# S3220A2.net
KiCad netlist of a schematic drawn in Altium Designer
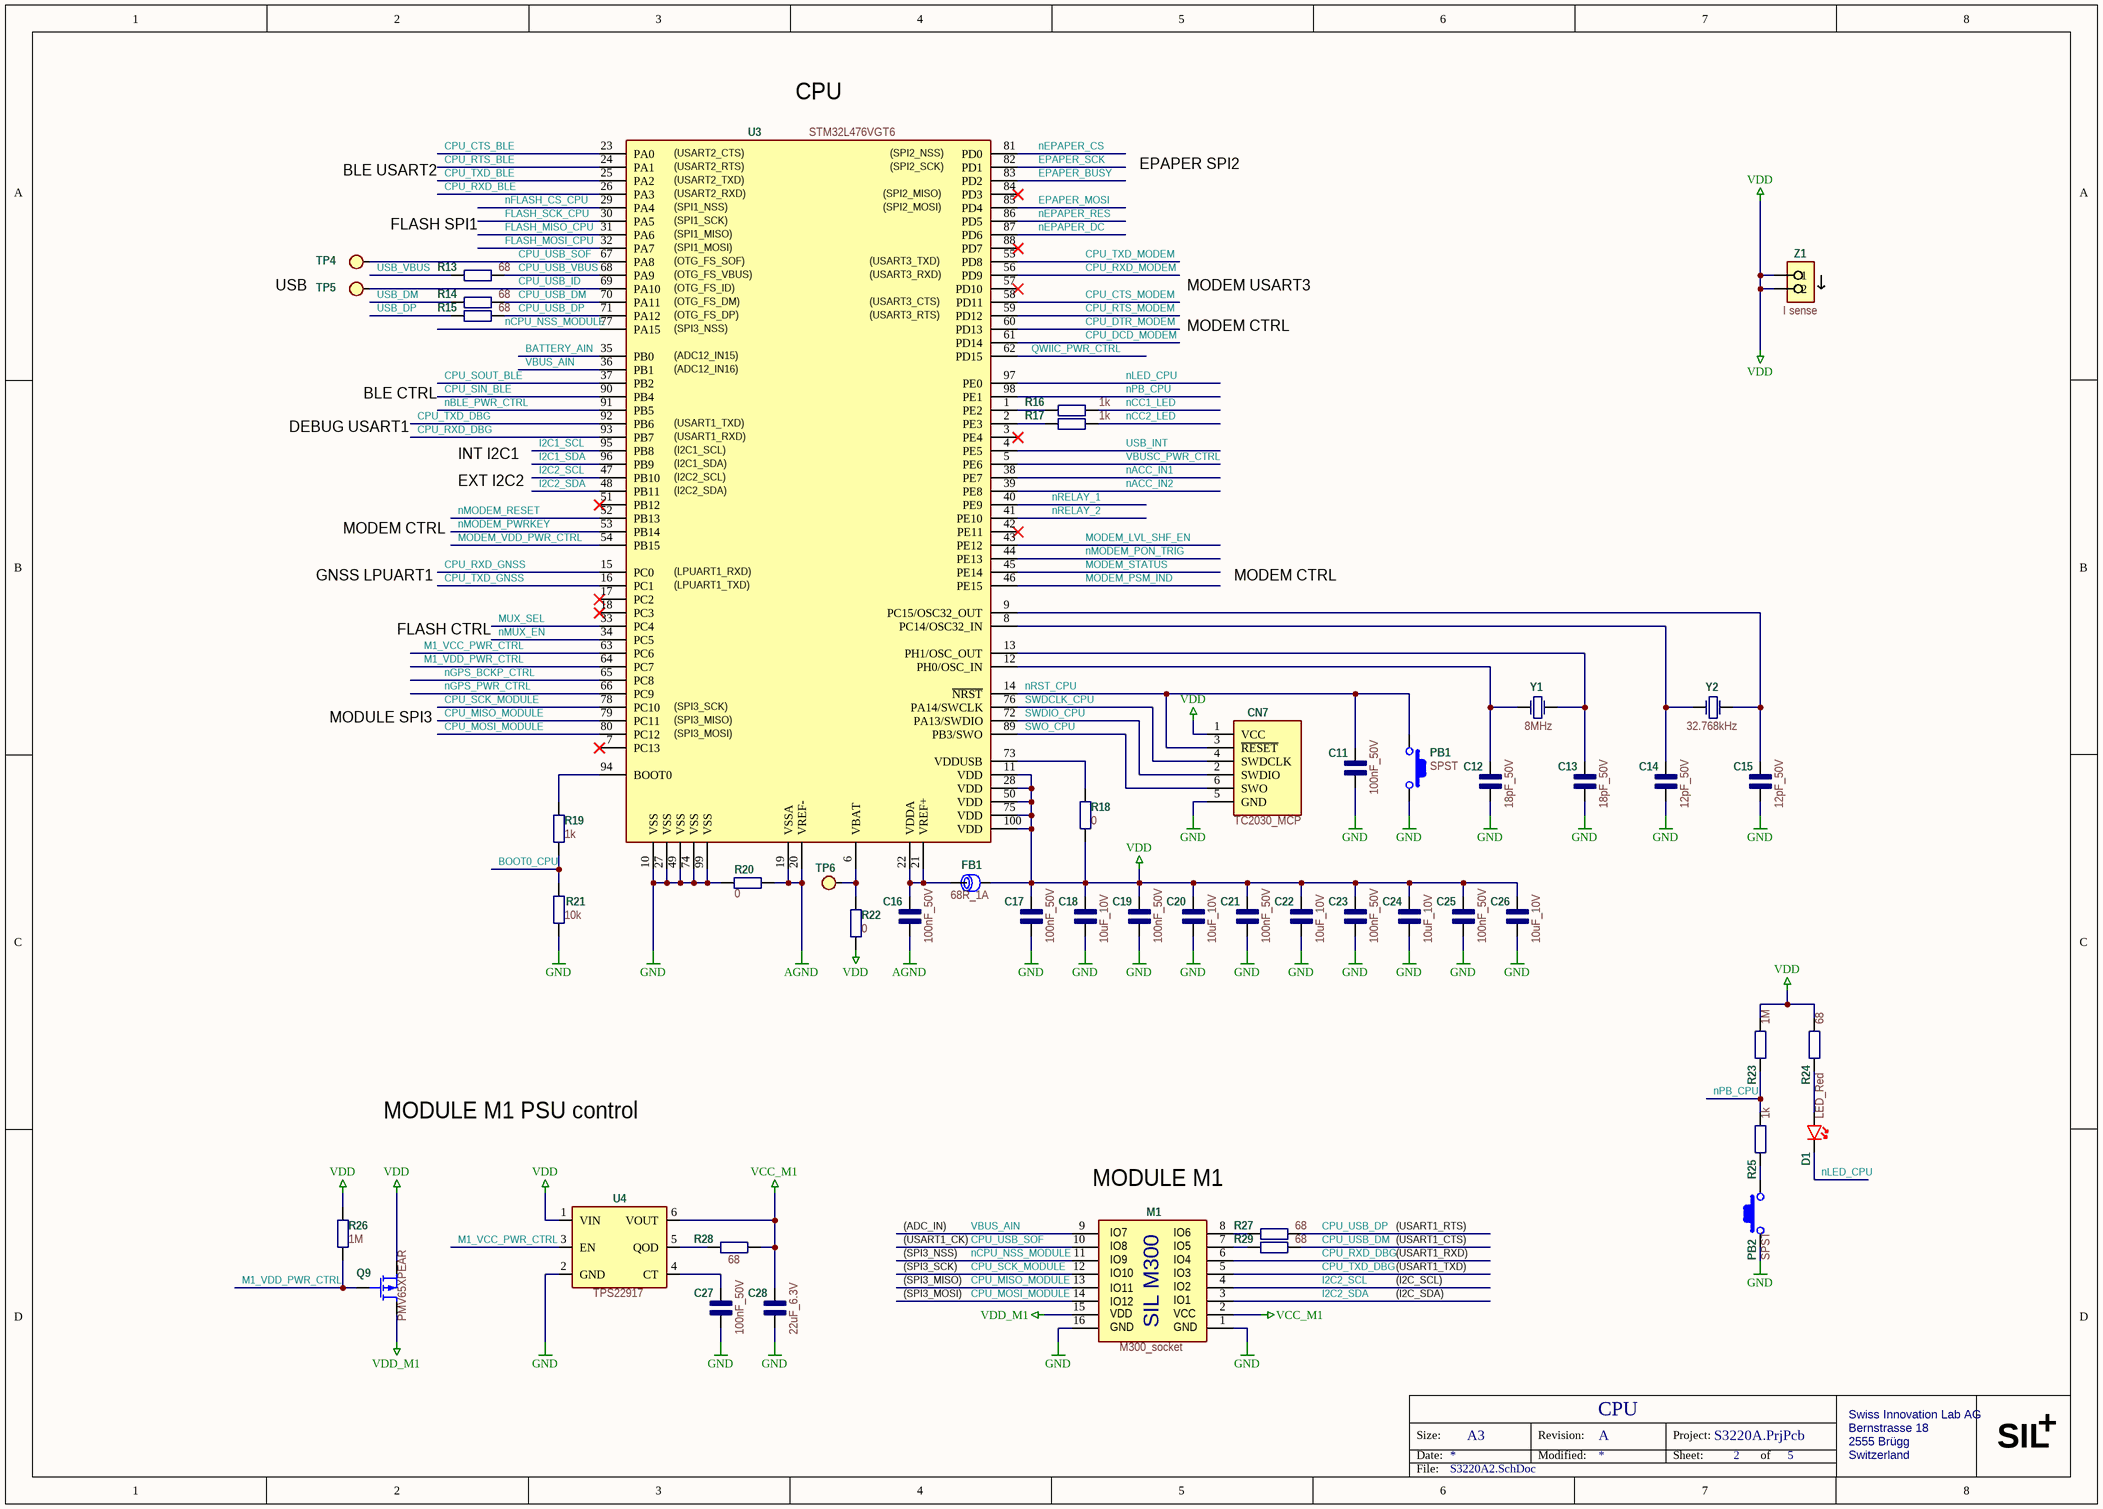
[diagram p0: S3220A2.SchDoc]

(export (version "E")
  (design (tool "Eeschema 10.0.6"))
  (components
    (comp (ref "C11")
      (value "100nF_50V")
      (footprint "SIL:C_0603")
      (description "0.1µF ±10% 50V Ceramic Capacitor X7R 0603 (1608 Metric)")
      (fields
        (field (name "MANUFACTURER") "TDK")
        (field (name "MANUFACTURER PART NUMBER") "C1608X7R1H104K080AA")
      )
      (libsource (lib "SIL") (part "C_100nF_50V"))
    )
    (comp (ref "C12")
      (value "18pF_50V")
      (footprint "SIL:C_0603")
      (description "18pF ±5% 50V Ceramic Capacitor C0G, NP0 0603 (1608 Metric)")
      (fields
        (field (name "MANUFACTURER") "KEMET")
        (field (name "MANUFACTURER PART NUMBER") "C0603C180J5GACTU")
      )
      (libsource (lib "SIL") (part "C_18pF_50V"))
    )
    (comp (ref "C13")
      (value "18pF_50V")
      (footprint "SIL:C_0603")
      (description "18pF ±5% 50V Ceramic Capacitor C0G, NP0 0603 (1608 Metric)")
      (fields
        (field (name "MANUFACTURER") "KEMET")
        (field (name "MANUFACTURER PART NUMBER") "C0603C180J5GACTU")
      )
      (libsource (lib "SIL") (part "C_18pF_50V"))
    )
    (comp (ref "C14")
      (value "12pF_50V")
      (footprint "SIL:C_0603")
      (description "12pF ±1% 50V Ceramic Capacitor C0G, NP0 0603 (1608 Metric)")
      (fields
        (field (name "MANUFACTURER") "Samsung Electro-Mechanics")
        (field (name "MANUFACTURER PART NUMBER") "CL10C120FB8NNNC")
      )
      (libsource (lib "SIL") (part "C_12pF_50V"))
    )
    (comp (ref "C15")
      (value "12pF_50V")
      (footprint "SIL:C_0603")
      (description "12pF ±1% 50V Ceramic Capacitor C0G, NP0 0603 (1608 Metric)")
      (fields
        (field (name "MANUFACTURER") "Samsung Electro-Mechanics")
        (field (name "MANUFACTURER PART NUMBER") "CL10C120FB8NNNC")
      )
      (libsource (lib "SIL") (part "C_12pF_50V"))
    )
    (comp (ref "C16")
      (value "100nF_50V")
      (footprint "SIL:C_0603")
      (description "0.1µF ±10% 50V Ceramic Capacitor X7R 0603 (1608 Metric)")
      (fields
        (field (name "MANUFACTURER") "TDK")
        (field (name "MANUFACTURER PART NUMBER") "C1608X7R1H104K080AA")
      )
      (libsource (lib "SIL") (part "C_100nF_50V"))
    )
    (comp (ref "C17")
      (value "100nF_50V")
      (footprint "SIL:C_0603")
      (description "0.1µF ±10% 50V Ceramic Capacitor X7R 0603 (1608 Metric)")
      (fields
        (field (name "MANUFACTURER") "TDK")
        (field (name "MANUFACTURER PART NUMBER") "C1608X7R1H104K080AA")
      )
      (libsource (lib "SIL") (part "C_100nF_50V"))
    )
    (comp (ref "C18")
      (value "10uF_10V")
      (footprint "SIL:C_0603")
      (description "10µF ±10% 10V Ceramic Capacitor X5R 0603 (1608 Metric)")
      (fields
        (field (name "MANUFACTURER") "Murata Electronics North America")
        (field (name "MANUFACTURER PART NUMBER") "GRM188R61A106KE69D")
      )
      (libsource (lib "SIL") (part "C_10uF_10V"))
    )
    (comp (ref "C19")
      (value "100nF_50V")
      (footprint "SIL:C_0603")
      (description "0.1µF ±10% 50V Ceramic Capacitor X7R 0603 (1608 Metric)")
      (fields
        (field (name "MANUFACTURER") "TDK")
        (field (name "MANUFACTURER PART NUMBER") "C1608X7R1H104K080AA")
      )
      (libsource (lib "SIL") (part "C_100nF_50V"))
    )
    (comp (ref "C20")
      (value "10uF_10V")
      (footprint "SIL:C_0603")
      (description "10µF ±10% 10V Ceramic Capacitor X5R 0603 (1608 Metric)")
      (fields
        (field (name "MANUFACTURER") "Murata Electronics North America")
        (field (name "MANUFACTURER PART NUMBER") "GRM188R61A106KE69D")
      )
      (libsource (lib "SIL") (part "C_10uF_10V"))
    )
    (comp (ref "C21")
      (value "100nF_50V")
      (footprint "SIL:C_0603")
      (description "0.1µF ±10% 50V Ceramic Capacitor X7R 0603 (1608 Metric)")
      (fields
        (field (name "MANUFACTURER") "TDK")
        (field (name "MANUFACTURER PART NUMBER") "C1608X7R1H104K080AA")
      )
      (libsource (lib "SIL") (part "C_100nF_50V"))
    )
    (comp (ref "C22")
      (value "10uF_10V")
      (footprint "SIL:C_0603")
      (description "10µF ±10% 10V Ceramic Capacitor X5R 0603 (1608 Metric)")
      (fields
        (field (name "MANUFACTURER") "Murata Electronics North America")
        (field (name "MANUFACTURER PART NUMBER") "GRM188R61A106KE69D")
      )
      (libsource (lib "SIL") (part "C_10uF_10V"))
    )
    (comp (ref "C23")
      (value "100nF_50V")
      (footprint "SIL:C_0603")
      (description "0.1µF ±10% 50V Ceramic Capacitor X7R 0603 (1608 Metric)")
      (fields
        (field (name "MANUFACTURER") "TDK")
        (field (name "MANUFACTURER PART NUMBER") "C1608X7R1H104K080AA")
      )
      (libsource (lib "SIL") (part "C_100nF_50V"))
    )
    (comp (ref "C24")
      (value "10uF_10V")
      (footprint "SIL:C_0603")
      (description "10µF ±10% 10V Ceramic Capacitor X5R 0603 (1608 Metric)")
      (fields
        (field (name "MANUFACTURER") "Murata Electronics North America")
        (field (name "MANUFACTURER PART NUMBER") "GRM188R61A106KE69D")
      )
      (libsource (lib "SIL") (part "C_10uF_10V"))
    )
    (comp (ref "C25")
      (value "100nF_50V")
      (footprint "SIL:C_0603")
      (description "0.1µF ±10% 50V Ceramic Capacitor X7R 0603 (1608 Metric)")
      (fields
        (field (name "MANUFACTURER") "TDK")
        (field (name "MANUFACTURER PART NUMBER") "C1608X7R1H104K080AA")
      )
      (libsource (lib "SIL") (part "C_100nF_50V"))
    )
    (comp (ref "C26")
      (value "10uF_10V")
      (footprint "SIL:C_0603")
      (description "10µF ±10% 10V Ceramic Capacitor X5R 0603 (1608 Metric)")
      (fields
        (field (name "MANUFACTURER") "Murata Electronics North America")
        (field (name "MANUFACTURER PART NUMBER") "GRM188R61A106KE69D")
      )
      (libsource (lib "SIL") (part "C_10uF_10V"))
    )
    (comp (ref "C27")
      (value "100nF_50V")
      (footprint "SIL:C_0603")
      (description "0.1µF ±10% 50V Ceramic Capacitor X7R 0603 (1608 Metric)")
      (fields
        (field (name "MANUFACTURER") "TDK")
        (field (name "MANUFACTURER PART NUMBER") "C1608X7R1H104K080AA")
      )
      (libsource (lib "SIL") (part "C_100nF_50V"))
    )
    (comp (ref "C28")
      (value "22uF_6.3V")
      (footprint "SIL:C_0603")
      (description "22µF ±20% 6.3V Ceramic Capacitor X5R 0603 (1608 Metric)")
      (fields
        (field (name "MANUFACTURER") "Samsung Electro-Mechanics")
        (field (name "MANUFACTURER PART NUMBER") "CL10A226MQ8NRNC")
      )
      (libsource (lib "SIL") (part "C_22uF_6V3"))
    )
    (comp (ref "CN7")
      (value "TC2030_MCP")
      (footprint "SIL:CN_TC2030-MCP-NL")
      (description "TC2030-MCP-NL")
      (libsource (lib "SIL") (part "CN_TC2030"))
    )
    (comp (ref "D1")
      (value "LED_Red")
      (footprint "LED_0603")
      (description "Red 631nm LED Indication - Discrete 2V 0603")
      (fields
        (field (name "MANUFACTURER") "Lite-On Inc.")
        (field (name "MANUFACTURER PART NUMBER") "LTST-C193KRKT-5A")
      )
      (libsource (lib "SIL") (part "D_LED_R_5mA"))
    )
    (comp (ref "FB1")
      (value "68R_1A")
      (footprint "SIL:L_0603")
      (description "FERRITE BEAD 68 OHM 0603 1LN")
      (fields
        (field (name "MANUFACTURER") "Laird-Signal Integrity Products")
        (field (name "MANUFACTURER PART NUMBER") "MI0603J680R-10")
      )
      (libsource (lib "SIL") (part "FB_68R_1A"))
    )
    (comp (ref "M1")
      (value "M300_socket")
      (footprint "M_M300_socket")
      (description "Module M300 motherboard socket")
      (fields
        (field (name "MANUFACTURER") "Swiss Innovation Lab")
        (field (name "MANUFACTURER PART NUMBER") "M300")
      )
      (libsource (lib "SIL") (part "M_M300_socket"))
    )
    (comp (ref "PB1")
      (value "SPST")
      (footprint "SIL:PB_PTS810")
      (description "Tactile Switch SPST-NO Top Actuated Surface Mount")
      (fields
        (field (name "MANUFACTURER") "C&K")
        (field (name "MANUFACTURER PART NUMBER") "PTS810 SJM 250 SMTR LFS")
      )
      (libsource (lib "SIL") (part "PB_SPST_2.5mm"))
    )
    (comp (ref "PB2")
      (value "SPST")
      (footprint "SIL:PB_PTS810")
      (description "Tactile Switch SPST-NO Top Actuated Surface Mount")
      (fields
        (field (name "MANUFACTURER") "C&K")
        (field (name "MANUFACTURER PART NUMBER") "PTS810 SJM 250 SMTR LFS")
      )
      (libsource (lib "SIL") (part "PB_SPST_2.5mm"))
    )
    (comp (ref "Q9")
      (value "PMV65XPEAR")
      (footprint "U_SOT23-3")
      (description "P-Channel 20V 2.8A (Ta) 480mW (Ta), 6.25W (Tc) Surface Mount TO-236AB (SOT23)")
      (fields (field (name "MANUFACTURER") "Nexperia USA Inc."))
      (libsource (lib "SIL") (part "Q_PMV65"))
    )
    (comp (ref "R13")
      (value "68")
      (footprint "SIL:R_0603")
      (description "68 Ohms ±1% 0.1W, 1/10W Chip Resistor 0603 (1608 Metric) Automotive AEC-Q200 Thick Film")
      (fields
        (field (name "MANUFACTURER") "Panasonic Electronic Components")
        (field (name "MANUFACTURER PART NUMBER") "ERJ-3EKF68R0V")
      )
      (libsource (lib "") (part "R_68_1%_1"))
    )
    (comp (ref "R14")
      (value "68")
      (footprint "SIL:R_0603")
      (description "68 Ohms ±1% 0.1W, 1/10W Chip Resistor 0603 (1608 Metric) Automotive AEC-Q200 Thick Film")
      (fields
        (field (name "MANUFACTURER") "Panasonic Electronic Components")
        (field (name "MANUFACTURER PART NUMBER") "ERJ-3EKF68R0V")
      )
      (libsource (lib "") (part "R_68_1%_1"))
    )
    (comp (ref "R15")
      (value "68")
      (footprint "SIL:R_0603")
      (description "68 Ohms ±1% 0.1W, 1/10W Chip Resistor 0603 (1608 Metric) Automotive AEC-Q200 Thick Film")
      (fields
        (field (name "MANUFACTURER") "Panasonic Electronic Components")
        (field (name "MANUFACTURER PART NUMBER") "ERJ-3EKF68R0V")
      )
      (libsource (lib "") (part "R_68_1%_1"))
    )
    (comp (ref "R16")
      (value "1k")
      (footprint "SIL:R_0603")
      (description "1 kOhms ±1% 0.1W, 1/10W Chip Resistor 0603 (1608 Metric) Automotive AEC-Q200 Thick Film")
      (fields
        (field (name "MANUFACTURER") "Panasonic Electronic Components")
        (field (name "MANUFACTURER PART NUMBER") "ERJ-3EKF1001V")
      )
      (libsource (lib "") (part "R_1k_1%_1"))
    )
    (comp (ref "R17")
      (value "1k")
      (footprint "SIL:R_0603")
      (description "1 kOhms ±1% 0.1W, 1/10W Chip Resistor 0603 (1608 Metric) Automotive AEC-Q200 Thick Film")
      (fields
        (field (name "MANUFACTURER") "Panasonic Electronic Components")
        (field (name "MANUFACTURER PART NUMBER") "ERJ-3EKF1001V")
      )
      (libsource (lib "") (part "R_1k_1%_1"))
    )
    (comp (ref "R18")
      (value "0")
      (footprint "SIL:R_0603")
      (description "0 Ohms Jumper 0.1W, 1/10W Chip Resistor 0603 (1608 Metric) Automotive AEC-Q200 Thick Film")
      (fields
        (field (name "MANUFACTURER") "Panasonic Electronic Components")
        (field (name "MANUFACTURER PART NUMBER") "ERJ-3GEY0R00V")
      )
      (libsource (lib "") (part "R_0_1%_1"))
    )
    (comp (ref "R19")
      (value "1k")
      (footprint "SIL:R_0603")
      (description "1 kOhms ±1% 0.1W, 1/10W Chip Resistor 0603 (1608 Metric) Automotive AEC-Q200 Thick Film")
      (fields
        (field (name "MANUFACTURER") "Panasonic Electronic Components")
        (field (name "MANUFACTURER PART NUMBER") "ERJ-3EKF1001V")
      )
      (libsource (lib "SIL") (part "R_1k_1%"))
    )
    (comp (ref "R20")
      (value "0")
      (footprint "SIL:R_0603")
      (description "0 Ohms Jumper 0.1W, 1/10W Chip Resistor 0603 (1608 Metric) Automotive AEC-Q200 Thick Film")
      (fields
        (field (name "MANUFACTURER") "Panasonic Electronic Components")
        (field (name "MANUFACTURER PART NUMBER") "ERJ-3GEY0R00V")
      )
      (libsource (lib "") (part "R_0_1%_2"))
    )
    (comp (ref "R21")
      (value "10k")
      (footprint "SIL:R_0603")
      (description "10 kOhms ±1% 0.1W, 1/10W Chip Resistor 0603 (1608 Metric) Automotive AEC-Q200 Thick Film")
      (fields
        (field (name "MANUFACTURER") "Panasonic Electronic Components")
        (field (name "MANUFACTURER PART NUMBER") "ERJ-3EKF1002V")
      )
      (libsource (lib "SIL") (part "R_10k_1%"))
    )
    (comp (ref "R22")
      (value "0")
      (footprint "SIL:R_0603")
      (description "0 Ohms Jumper 0.1W, 1/10W Chip Resistor 0603 (1608 Metric) Automotive AEC-Q200 Thick Film")
      (fields
        (field (name "MANUFACTURER") "Panasonic Electronic Components")
        (field (name "MANUFACTURER PART NUMBER") "ERJ-3GEY0R00V")
      )
      (libsource (lib "SIL") (part "R_0_1%"))
    )
    (comp (ref "R23")
      (value "1M")
      (footprint "SIL:R_0603")
      (description "1 MOhms ±1% 0.1W, 1/10W Chip Resistor 0603 (1608 Metric) Automotive AEC-Q200 Thick Film")
      (fields
        (field (name "MANUFACTURER") "Panasonic Electronic Components")
        (field (name "MANUFACTURER PART NUMBER") "ERJ-3EKF1004V")
      )
      (libsource (lib "") (part "R_1M_1%_1"))
    )
    (comp (ref "R24")
      (value "68")
      (footprint "SIL:R_0603")
      (description "68 Ohms ±1% 0.1W, 1/10W Chip Resistor 0603 (1608 Metric) Automotive AEC-Q200 Thick Film")
      (fields
        (field (name "MANUFACTURER") "Panasonic Electronic Components")
        (field (name "MANUFACTURER PART NUMBER") "ERJ-3EKF68R0V")
      )
      (libsource (lib "SIL") (part "R_68_1%"))
    )
    (comp (ref "R25")
      (value "1k")
      (footprint "SIL:R_0603")
      (description "1 kOhms ±1% 0.1W, 1/10W Chip Resistor 0603 (1608 Metric) Automotive AEC-Q200 Thick Film")
      (fields
        (field (name "MANUFACTURER") "Panasonic Electronic Components")
        (field (name "MANUFACTURER PART NUMBER") "ERJ-3EKF1001V")
      )
      (libsource (lib "SIL") (part "R_1k_1%"))
    )
    (comp (ref "R26")
      (value "1M")
      (footprint "SIL:R_0603")
      (description "1 MOhms ±1% 0.1W, 1/10W Chip Resistor 0603 (1608 Metric) Automotive AEC-Q200 Thick Film")
      (fields
        (field (name "MANUFACTURER") "Panasonic Electronic Components")
        (field (name "MANUFACTURER PART NUMBER") "ERJ-3EKF1004V")
      )
      (libsource (lib "SIL") (part "R_1M_1%"))
    )
    (comp (ref "R27")
      (value "68")
      (footprint "SIL:R_0603")
      (description "68 Ohms ±1% 0.1W, 1/10W Chip Resistor 0603 (1608 Metric) Automotive AEC-Q200 Thick Film")
      (fields
        (field (name "MANUFACTURER") "Panasonic Electronic Components")
        (field (name "MANUFACTURER PART NUMBER") "ERJ-3EKF68R0V")
      )
      (libsource (lib "") (part "R_68_1%_1"))
    )
    (comp (ref "R28")
      (value "68")
      (footprint "SIL:R_0603")
      (description "68 Ohms ±1% 0.1W, 1/10W Chip Resistor 0603 (1608 Metric) Automotive AEC-Q200 Thick Film")
      (fields
        (field (name "MANUFACTURER") "Panasonic Electronic Components")
        (field (name "MANUFACTURER PART NUMBER") "ERJ-3EKF68R0V")
      )
      (libsource (lib "") (part "R_68_1%_2"))
    )
    (comp (ref "R29")
      (value "68")
      (footprint "SIL:R_0603")
      (description "68 Ohms ±1% 0.1W, 1/10W Chip Resistor 0603 (1608 Metric) Automotive AEC-Q200 Thick Film")
      (fields
        (field (name "MANUFACTURER") "Panasonic Electronic Components")
        (field (name "MANUFACTURER PART NUMBER") "ERJ-3EKF68R0V")
      )
      (libsource (lib "") (part "R_68_1%_1"))
    )
    (comp (ref "TP4")
      (value "Test point")
      (footprint "SIL:TP_SMD_R1.0mm")
      (fields (field (name "MANUFACTURER") "Swiss Innovation Lab"))
      (libsource (lib "SIL") (part "TP_Test_point"))
    )
    (comp (ref "TP5")
      (value "Test point")
      (footprint "SIL:TP_SMD_R1.0mm")
      (fields (field (name "MANUFACTURER") "Swiss Innovation Lab"))
      (libsource (lib "SIL") (part "TP_Test_point"))
    )
    (comp (ref "TP6")
      (value "Test point")
      (footprint "SIL:TP_SMD_R1.0mm")
      (fields (field (name "MANUFACTURER") "Swiss Innovation Lab"))
      (libsource (lib "SIL") (part "TP_Test_point"))
    )
    (comp (ref "U3")
      (value "STM32L476VGT6")
      (footprint "SIL:U_100-LQFP")
      (description "ARM® Cortex®-M4 STM32L4 Microcontroller IC 32-Bit 80MHz 1MB (1M x 8) FLASH 100-LQFP (14x14)")
      (fields (field (name "MANUFACTURER") "STMicroelectronics"))
      (libsource (lib "SIL") (part "U_STM32L476"))
    )
    (comp (ref "U4")
      (value "TPS22917")
      (footprint "U_SOT23-6")
      (description "Power Switch/Driver 1:1 P-Channel 2A SOT-23-6")
      (fields
        (field (name "MANUFACTURER") "Texas Instruments")
        (field (name "MANUFACTURER PART NUMBER") "TPS22917DBVR")
      )
      (libsource (lib "SIL") (part "U_TPS22917"))
    )
    (comp (ref "Y1")
      (value "8MHz")
      (footprint "SIL:Y_ABMM2")
      (description "8MHz ±20ppm Crystal 18pF 72 Ohms 4-SMD, No Lead")
      (fields
        (field (name "MANUFACTURER") "Abracon LLC")
        (field (name "MANUFACTURER PART NUMBER") "ABMM2-8.000MHZ-E2-T")
      )
      (libsource (lib "SIL") (part "Y_8MHz_20ppm"))
    )
    (comp (ref "Y2")
      (value "32.768kHz")
      (footprint "SIL:Y_XTAL-3215")
      (description "32.768kHz ±10ppm Crystal 12.5pF 70 kOhms 2-SMD, No Lead")
      (fields
        (field (name "MANUFACTURER") "ECS Inc.")
        (field (name "MANUFACTURER PART NUMBER") "ECS-.327-12.5-34B-C-TR")
      )
      (libsource (lib "SIL") (part "Y_32kHz_10ppm"))
    )
    (comp (ref "Z1")
      (value "I sense")
      (footprint "Z_I_SENSE")
      (description "2 Positions Header Connector 0.100\" (2.54mm) SMD Gold for current measurement")
      (fields (field (name "MANUFACTURER") "SIL"))
      (libsource (lib "SIL") (part "Z_I_sense"))
    )
  )
  (nets
    (net (code "1") (name "/BATTERY_AIN") (class "Default")
      (node (ref "U3") (pin "35") (pinfunction "PB0_35") (pintype "passive"))
    )
    (net (code "2") (name "/BOOT0_CPU") (class "Default")
      (node (ref "R19") (pin "1") (pinfunction "1_1") (pintype "passive"))
      (node (ref "R21") (pin "2") (pinfunction "2_2") (pintype "passive"))
    )
    (net (code "3") (name "/CPU_CTS_BLE") (class "Default")
      (node (ref "U3") (pin "23") (pinfunction "PA0_23") (pintype "passive"))
    )
    (net (code "4") (name "/CPU_CTS_MODEM") (class "Default")
      (node (ref "U3") (pin "58") (pinfunction "PD11_58") (pintype "passive"))
    )
    (net (code "5") (name "/CPU_DCD_MODEM") (class "Default")
      (node (ref "U3") (pin "61") (pinfunction "PD14_61") (pintype "passive"))
    )
    (net (code "6") (name "/CPU_DTR_MODEM") (class "Default")
      (node (ref "U3") (pin "60") (pinfunction "PD13_60") (pintype "passive"))
    )
    (net (code "7") (name "/CPU_MISO_MODULE") (class "Default")
      (node (ref "M1") (pin "13") (pinfunction "MISO_13") (pintype "passive"))
      (node (ref "U3") (pin "79") (pinfunction "PC11_79") (pintype "passive"))
    )
    (net (code "8") (name "/CPU_MOSI_MODULE") (class "Default")
      (node (ref "M1") (pin "14") (pinfunction "MOSI_14") (pintype "passive"))
      (node (ref "U3") (pin "80") (pinfunction "PC12_80") (pintype "passive"))
    )
    (net (code "9") (name "/CPU_RTS_BLE") (class "Default")
      (node (ref "U3") (pin "24") (pinfunction "PA1_24") (pintype "passive"))
    )
    (net (code "10") (name "/CPU_RTS_MODEM") (class "Default")
      (node (ref "U3") (pin "59") (pinfunction "PD12_59") (pintype "passive"))
    )
    (net (code "11") (name "/CPU_RXD_BLE") (class "Default")
      (node (ref "U3") (pin "26") (pinfunction "PA3_26") (pintype "passive"))
    )
    (net (code "12") (name "/CPU_RXD_DBG") (class "Default")
      (node (ref "M1") (pin "6") (pinfunction "RX_6") (pintype "passive"))
      (node (ref "U3") (pin "93") (pinfunction "PB7_93") (pintype "passive"))
    )
    (net (code "13") (name "/CPU_RXD_GNSS") (class "Default")
      (node (ref "U3") (pin "15") (pinfunction "PC0_15") (pintype "passive"))
    )
    (net (code "14") (name "/CPU_RXD_MODEM") (class "Default")
      (node (ref "U3") (pin "56") (pinfunction "PD9_56") (pintype "passive"))
    )
    (net (code "15") (name "/CPU_SCK_MODULE") (class "Default")
      (node (ref "M1") (pin "12") (pinfunction "SCK_12") (pintype "passive"))
      (node (ref "U3") (pin "78") (pinfunction "PC10_78") (pintype "passive"))
    )
    (net (code "16") (name "/CPU_SIN_BLE") (class "Default")
      (node (ref "U3") (pin "90") (pinfunction "PB4_90") (pintype "passive"))
    )
    (net (code "17") (name "/CPU_SOUT_BLE") (class "Default")
      (node (ref "U3") (pin "37") (pinfunction "PB2_37") (pintype "passive"))
    )
    (net (code "18") (name "/CPU_TXD_BLE") (class "Default")
      (node (ref "U3") (pin "25") (pinfunction "PA2_25") (pintype "passive"))
    )
    (net (code "19") (name "/CPU_TXD_DBG") (class "Default")
      (node (ref "M1") (pin "5") (pinfunction "TX_5") (pintype "passive"))
      (node (ref "U3") (pin "92") (pinfunction "PB6_92") (pintype "passive"))
    )
    (net (code "20") (name "/CPU_TXD_GNSS") (class "Default")
      (node (ref "U3") (pin "16") (pinfunction "PC1_16") (pintype "passive"))
    )
    (net (code "21") (name "/CPU_TXD_MODEM") (class "Default")
      (node (ref "U3") (pin "55") (pinfunction "PD8_55") (pintype "passive"))
    )
    (net (code "22") (name "/CPU_USB_DM") (class "Default")
      (node (ref "R14") (pin "2") (pinfunction "2_2") (pintype "passive"))
      (node (ref "R29") (pin "2") (pinfunction "2_2") (pintype "passive"))
      (node (ref "U3") (pin "70") (pinfunction "PA11_70") (pintype "passive"))
    )
    (net (code "23") (name "/CPU_USB_DP") (class "Default")
      (node (ref "R15") (pin "2") (pinfunction "2_2") (pintype "passive"))
      (node (ref "R27") (pin "2") (pinfunction "2_2") (pintype "passive"))
      (node (ref "U3") (pin "71") (pinfunction "PA12_71") (pintype "passive"))
    )
    (net (code "24") (name "/CPU_USB_ID") (class "Default")
      (node (ref "TP5") (pin "1") (pinfunction "1_1") (pintype "passive"))
      (node (ref "U3") (pin "69") (pinfunction "PA10_69") (pintype "passive"))
    )
    (net (code "25") (name "/CPU_USB_SOF") (class "Default")
      (node (ref "M1") (pin "10") (pinfunction "RST_10") (pintype "passive"))
      (node (ref "TP4") (pin "1") (pinfunction "1_1") (pintype "passive"))
      (node (ref "U3") (pin "67") (pinfunction "PA8_67") (pintype "passive"))
    )
    (net (code "26") (name "/CPU_USB_VBUS") (class "Default")
      (node (ref "R13") (pin "2") (pinfunction "2_2") (pintype "passive"))
      (node (ref "U3") (pin "68") (pinfunction "PA9_68") (pintype "passive"))
    )
    (net (code "27") (name "/EPAPER_BUSY") (class "Default")
      (node (ref "U3") (pin "83") (pinfunction "PD2_83") (pintype "passive"))
    )
    (net (code "28") (name "/EPAPER_MOSI") (class "Default")
      (node (ref "U3") (pin "85") (pinfunction "PD4_85") (pintype "passive"))
    )
    (net (code "29") (name "/EPAPER_SCK") (class "Default")
      (node (ref "U3") (pin "82") (pinfunction "PD1_82") (pintype "passive"))
    )
    (net (code "30") (name "/FLASH_MISO_CPU") (class "Default")
      (node (ref "U3") (pin "31") (pinfunction "PA6_31") (pintype "passive"))
    )
    (net (code "31") (name "/FLASH_MOSI_CPU") (class "Default")
      (node (ref "U3") (pin "32") (pinfunction "PA7_32") (pintype "passive"))
    )
    (net (code "32") (name "/FLASH_SCK_CPU") (class "Default")
      (node (ref "U3") (pin "30") (pinfunction "PA5_30") (pintype "passive"))
    )
    (net (code "33") (name "/I2C1_SCL") (class "Default")
      (node (ref "U3") (pin "95") (pinfunction "PB8_95") (pintype "passive"))
    )
    (net (code "34") (name "/I2C1_SDA") (class "Default")
      (node (ref "U3") (pin "96") (pinfunction "PB9_96") (pintype "passive"))
    )
    (net (code "35") (name "/I2C2_SCL") (class "Default")
      (node (ref "M1") (pin "4") (pinfunction "SCL_4") (pintype "passive"))
      (node (ref "U3") (pin "47") (pinfunction "PB10_47") (pintype "passive"))
    )
    (net (code "36") (name "/I2C2_SDA") (class "Default")
      (node (ref "M1") (pin "3") (pinfunction "SDA_3") (pintype "passive"))
      (node (ref "U3") (pin "48") (pinfunction "PB11_48") (pintype "passive"))
    )
    (net (code "37") (name "/M1_VCC_PWR_CTRL") (class "Default")
      (node (ref "U3") (pin "63") (pinfunction "PC6_63") (pintype "passive"))
      (node (ref "U4") (pin "3") (pinfunction "EN_3") (pintype "passive"))
    )
    (net (code "38") (name "/M1_VDD_PWR_CTRL") (class "Default")
      (node (ref "Q9") (pin "1") (pinfunction "G_1") (pintype "passive"))
      (node (ref "R26") (pin "1") (pinfunction "1_1") (pintype "passive"))
      (node (ref "U3") (pin "64") (pinfunction "PC7_64") (pintype "passive"))
    )
    (net (code "39") (name "/MODEM_LVL_SHF_EN") (class "Default")
      (node (ref "U3") (pin "43") (pinfunction "PE12_43") (pintype "passive"))
    )
    (net (code "40") (name "/MODEM_PSM_IND") (class "Default")
      (node (ref "U3") (pin "46") (pinfunction "PE15_46") (pintype "passive"))
    )
    (net (code "41") (name "/MODEM_STATUS") (class "Default")
      (node (ref "U3") (pin "45") (pinfunction "PE14_45") (pintype "passive"))
    )
    (net (code "42") (name "/MODEM_VDD_PWR_CTRL") (class "Default")
      (node (ref "U3") (pin "54") (pinfunction "PB15_54") (pintype "passive"))
    )
    (net (code "43") (name "/MUX_SEL") (class "Default")
      (node (ref "U3") (pin "33") (pinfunction "PC4_33") (pintype "passive"))
    )
    (net (code "44") (name "/QWIIC_PWR_CTRL") (class "Default")
      (node (ref "U3") (pin "62") (pinfunction "PD15_62") (pintype "passive"))
    )
    (net (code "45") (name "/SWDCLK_CPU") (class "Default")
      (node (ref "CN7") (pin "4") (pinfunction "SWDCLK_4") (pintype "passive"))
      (node (ref "U3") (pin "76") (pinfunction "PA14/SWCLK_76") (pintype "passive"))
    )
    (net (code "46") (name "/SWDIO_CPU") (class "Default")
      (node (ref "CN7") (pin "2") (pinfunction "SWDIO_2") (pintype "passive"))
      (node (ref "U3") (pin "72") (pinfunction "PA13/SWDIO_72") (pintype "passive"))
    )
    (net (code "47") (name "/SWO_CPU") (class "Default")
      (node (ref "CN7") (pin "6") (pinfunction "SWO_6") (pintype "passive"))
      (node (ref "U3") (pin "89") (pinfunction "PB3/SWO_89") (pintype "passive"))
    )
    (net (code "48") (name "/USB_DM") (class "Default")
      (node (ref "R14") (pin "1") (pinfunction "1_1") (pintype "passive"))
    )
    (net (code "49") (name "/USB_DP") (class "Default")
      (node (ref "R15") (pin "1") (pinfunction "1_1") (pintype "passive"))
    )
    (net (code "50") (name "/USB_INT") (class "Default")
      (node (ref "U3") (pin "4") (pinfunction "PE5_4") (pintype "passive"))
    )
    (net (code "51") (name "/USB_VBUS") (class "Default")
      (node (ref "R13") (pin "1") (pinfunction "1_1") (pintype "passive"))
    )
    (net (code "52") (name "/VBUSC_PWR_CTRL") (class "Default")
      (node (ref "U3") (pin "5") (pinfunction "PE6_5") (pintype "passive"))
    )
    (net (code "53") (name "/VBUS_AIN") (class "Default")
      (node (ref "M1") (pin "9") (pinfunction "AN_9") (pintype "passive"))
      (node (ref "U3") (pin "36") (pinfunction "PB1_36") (pintype "passive"))
    )
    (net (code "54") (name "/nACC_IN1") (class "Default")
      (node (ref "U3") (pin "38") (pinfunction "PE7_38") (pintype "passive"))
    )
    (net (code "55") (name "/nACC_IN2") (class "Default")
      (node (ref "U3") (pin "39") (pinfunction "PE8_39") (pintype "passive"))
    )
    (net (code "56") (name "/nBLE_PWR_CTRL") (class "Default")
      (node (ref "U3") (pin "91") (pinfunction "PB5_91") (pintype "passive"))
    )
    (net (code "57") (name "/nCC1_LED") (class "Default")
      (node (ref "R16") (pin "1") (pinfunction "1_1") (pintype "passive"))
    )
    (net (code "58") (name "/nCC2_LED") (class "Default")
      (node (ref "R17") (pin "1") (pinfunction "1_1") (pintype "passive"))
    )
    (net (code "59") (name "/nCPU_NSS_MODULE") (class "Default")
      (node (ref "M1") (pin "11") (pinfunction "CS_11") (pintype "passive"))
      (node (ref "U3") (pin "77") (pinfunction "PA15_77") (pintype "passive"))
    )
    (net (code "60") (name "/nEPAPER_CS") (class "Default")
      (node (ref "U3") (pin "81") (pinfunction "PD0_81") (pintype "passive"))
    )
    (net (code "61") (name "/nEPAPER_DC") (class "Default")
      (node (ref "U3") (pin "87") (pinfunction "PD6_87") (pintype "passive"))
    )
    (net (code "62") (name "/nEPAPER_RES") (class "Default")
      (node (ref "U3") (pin "86") (pinfunction "PD5_86") (pintype "passive"))
    )
    (net (code "63") (name "/nFLASH_CS_CPU") (class "Default")
      (node (ref "U3") (pin "29") (pinfunction "PA4_29") (pintype "passive"))
    )
    (net (code "64") (name "/nGPS_BCKP_CTRL") (class "Default")
      (node (ref "U3") (pin "65") (pinfunction "PC8_65") (pintype "passive"))
    )
    (net (code "65") (name "/nGPS_PWR_CTRL") (class "Default")
      (node (ref "U3") (pin "66") (pinfunction "PC9_66") (pintype "passive"))
    )
    (net (code "66") (name "/nLED_CPU") (class "Default")
      (node (ref "D1") (pin "2") (pinfunction "K_2") (pintype "passive"))
      (node (ref "U3") (pin "97") (pinfunction "PE0_97") (pintype "passive"))
    )
    (net (code "67") (name "/nMODEM_PON_TRIG") (class "Default")
      (node (ref "U3") (pin "44") (pinfunction "PE13_44") (pintype "passive"))
    )
    (net (code "68") (name "/nMODEM_PWRKEY") (class "Default")
      (node (ref "U3") (pin "53") (pinfunction "PB14_53") (pintype "passive"))
    )
    (net (code "69") (name "/nMODEM_RESET") (class "Default")
      (node (ref "U3") (pin "52") (pinfunction "PB13_52") (pintype "passive"))
    )
    (net (code "70") (name "/nMUX_EN") (class "Default")
      (node (ref "U3") (pin "34") (pinfunction "PC5_34") (pintype "passive"))
    )
    (net (code "71") (name "/nPB_CPU") (class "Default")
      (node (ref "R23") (pin "2") (pinfunction "2_2") (pintype "passive"))
      (node (ref "R25") (pin "2") (pinfunction "2_2") (pintype "passive"))
      (node (ref "U3") (pin "98") (pinfunction "PE1_98") (pintype "passive"))
    )
    (net (code "72") (name "/nRELAY_1") (class "Default")
      (node (ref "U3") (pin "40") (pinfunction "PE9_40") (pintype "passive"))
    )
    (net (code "73") (name "/nRELAY_2") (class "Default")
      (node (ref "U3") (pin "41") (pinfunction "PE10_41") (pintype "passive"))
    )
    (net (code "74") (name "/nRST_CPU") (class "Default")
      (node (ref "C11") (pin "2") (pintype "passive"))
      (node (ref "CN7") (pin "3") (pinfunction "~{RESET}_3") (pintype "passive"))
      (node (ref "PB1") (pin "2") (pinfunction "2_2") (pintype "passive"))
      (node (ref "U3") (pin "14") (pinfunction "~{NRST}_14") (pintype "passive"))
    )
    (net (code "75") (name "AGND") (class "Default")
      (node (ref "C16") (pin "1") (pintype "passive"))
      (node (ref "R20") (pin "2") (pinfunction "2_2") (pintype "passive"))
      (node (ref "U3") (pin "19") (pinfunction "VSSA_19") (pintype "passive"))
      (node (ref "U3") (pin "20") (pinfunction "VREF-_20") (pintype "passive"))
    )
    (net (code "76") (name "GND") (class "Default")
      (node (ref "C11") (pin "1") (pintype "passive"))
      (node (ref "C12") (pin "1") (pintype "passive"))
      (node (ref "C13") (pin "1") (pintype "passive"))
      (node (ref "C14") (pin "1") (pintype "passive"))
      (node (ref "C15") (pin "1") (pintype "passive"))
      (node (ref "C17") (pin "1") (pintype "passive"))
      (node (ref "C18") (pin "1") (pintype "passive"))
      (node (ref "C19") (pin "1") (pintype "passive"))
      (node (ref "C20") (pin "1") (pintype "passive"))
      (node (ref "C21") (pin "1") (pintype "passive"))
      (node (ref "C22") (pin "1") (pintype "passive"))
      (node (ref "C23") (pin "1") (pintype "passive"))
      (node (ref "C24") (pin "1") (pintype "passive"))
      (node (ref "C25") (pin "1") (pintype "passive"))
      (node (ref "C26") (pin "1") (pintype "passive"))
      (node (ref "C27") (pin "1") (pintype "passive"))
      (node (ref "C28") (pin "1") (pintype "passive"))
      (node (ref "CN7") (pin "5") (pinfunction "GND_5") (pintype "passive"))
      (node (ref "M1") (pin "1") (pinfunction "GND_1") (pintype "passive"))
      (node (ref "M1") (pin "16") (pinfunction "GND_16") (pintype "passive"))
      (node (ref "PB1") (pin "1") (pinfunction "1_1") (pintype "passive"))
      (node (ref "PB2") (pin "2") (pinfunction "2_2") (pintype "passive"))
      (node (ref "R20") (pin "1") (pinfunction "1_1") (pintype "passive"))
      (node (ref "R21") (pin "1") (pinfunction "1_1") (pintype "passive"))
      (node (ref "U3") (pin "10") (pinfunction "VSS_10") (pintype "passive"))
      (node (ref "U3") (pin "27") (pinfunction "VSS_27") (pintype "passive"))
      (node (ref "U3") (pin "49") (pinfunction "VSS_49") (pintype "passive"))
      (node (ref "U3") (pin "74") (pinfunction "VSS_74") (pintype "passive"))
      (node (ref "U3") (pin "99") (pinfunction "VSS_99") (pintype "passive"))
      (node (ref "U4") (pin "2") (pinfunction "GND_2") (pintype "power_in"))
    )
    (net (code "77") (name "Net-(D1-A)") (class "Default")
      (node (ref "D1") (pin "1") (pinfunction "A_1") (pintype "passive"))
      (node (ref "R24") (pin "1") (pinfunction "1_1") (pintype "passive"))
    )
    (net (code "78") (name "Net-(M1-INT)") (class "Default")
      (node (ref "M1") (pin "7") (pinfunction "INT_7") (pintype "passive"))
      (node (ref "R29") (pin "1") (pinfunction "1_1") (pintype "passive"))
    )
    (net (code "79") (name "Net-(M1-PWM)") (class "Default")
      (node (ref "M1") (pin "8") (pinfunction "PWM_8") (pintype "passive"))
      (node (ref "R27") (pin "1") (pinfunction "1_1") (pintype "passive"))
    )
    (net (code "80") (name "Net-(PB2-Pad1)") (class "Default")
      (node (ref "PB2") (pin "1") (pinfunction "1_1") (pintype "passive"))
      (node (ref "R25") (pin "1") (pinfunction "1_1") (pintype "passive"))
    )
    (net (code "81") (name "Net-(U3-BOOT0)") (class "Default")
      (node (ref "R19") (pin "2") (pinfunction "2_2") (pintype "passive"))
      (node (ref "U3") (pin "94") (pinfunction "BOOT0_94") (pintype "passive"))
    )
    (net (code "82") (name "Net-(U3-PC14{slash}OSC32_IN)") (class "Default")
      (node (ref "C14") (pin "2") (pintype "passive"))
      (node (ref "U3") (pin "8") (pinfunction "PC14/OSC32_IN_8") (pintype "passive"))
      (node (ref "Y2") (pin "1") (pinfunction "inp_1") (pintype "passive"))
    )
    (net (code "83") (name "Net-(U3-PC15{slash}OSC32_OUT)") (class "Default")
      (node (ref "C15") (pin "2") (pintype "passive"))
      (node (ref "U3") (pin "9") (pinfunction "PC15/OSC32_OUT_9") (pintype "passive"))
      (node (ref "Y2") (pin "2") (pinfunction "out_2") (pintype "passive"))
    )
    (net (code "84") (name "Net-(U3-PE2)") (class "Default")
      (node (ref "R16") (pin "2") (pinfunction "2_2") (pintype "passive"))
      (node (ref "U3") (pin "1") (pinfunction "PE2_1") (pintype "passive"))
    )
    (net (code "85") (name "Net-(U3-PE3)") (class "Default")
      (node (ref "R17") (pin "2") (pinfunction "2_2") (pintype "passive"))
      (node (ref "U3") (pin "2") (pinfunction "PE3_2") (pintype "passive"))
    )
    (net (code "86") (name "Net-(U3-PH0{slash}OSC_IN)") (class "Default")
      (node (ref "C12") (pin "2") (pintype "passive"))
      (node (ref "U3") (pin "12") (pinfunction "PH0/OSC_IN_12") (pintype "passive"))
      (node (ref "Y1") (pin "1") (pinfunction "inp_1") (pintype "passive"))
    )
    (net (code "87") (name "Net-(U3-PH1{slash}OSC_OUT)") (class "Default")
      (node (ref "C13") (pin "2") (pintype "passive"))
      (node (ref "U3") (pin "13") (pinfunction "PH1/OSC_OUT_13") (pintype "passive"))
      (node (ref "Y1") (pin "3") (pinfunction "out_3") (pintype "passive"))
    )
    (net (code "88") (name "Net-(U3-VBAT)") (class "Default")
      (node (ref "R22") (pin "2") (pinfunction "2_2") (pintype "passive"))
      (node (ref "TP6") (pin "1") (pinfunction "1_1") (pintype "passive"))
      (node (ref "U3") (pin "6") (pinfunction "VBAT_6") (pintype "passive"))
    )
    (net (code "89") (name "Net-(U3-VDDA)") (class "Default")
      (node (ref "C16") (pin "2") (pintype "passive"))
      (node (ref "FB1") (pin "1") (pintype "passive"))
      (node (ref "U3") (pin "21") (pinfunction "VREF+_21") (pintype "passive"))
      (node (ref "U3") (pin "22") (pinfunction "VDDA_22") (pintype "power_in"))
    )
    (net (code "90") (name "Net-(U3-VDDUSB)") (class "Default")
      (node (ref "R18") (pin "1") (pinfunction "1_1") (pintype "passive"))
      (node (ref "U3") (pin "73") (pinfunction "VDDUSB_73") (pintype "power_in"))
    )
    (net (code "91") (name "Net-(U4-CT)") (class "Default")
      (node (ref "C27") (pin "2") (pintype "passive"))
      (node (ref "U4") (pin "4") (pinfunction "CT_4") (pintype "passive"))
    )
    (net (code "92") (name "Net-(U4-QOD)") (class "Default")
      (node (ref "R28") (pin "2") (pinfunction "2_2") (pintype "passive"))
      (node (ref "U4") (pin "5") (pinfunction "QOD_5") (pintype "passive"))
    )
    (net (code "93") (name "VCC_M1") (class "Default")
      (node (ref "C28") (pin "2") (pintype "passive"))
      (node (ref "M1") (pin "2") (pinfunction "5V_2") (pintype "passive"))
      (node (ref "R28") (pin "1") (pinfunction "1_1") (pintype "passive"))
      (node (ref "U4") (pin "6") (pinfunction "VOUT_6") (pintype "passive"))
    )
    (net (code "94") (name "VDD") (class "Default")
      (node (ref "C17") (pin "2") (pintype "passive"))
      (node (ref "C18") (pin "2") (pintype "passive"))
      (node (ref "C19") (pin "2") (pintype "passive"))
      (node (ref "C20") (pin "2") (pintype "passive"))
      (node (ref "C21") (pin "2") (pintype "passive"))
      (node (ref "C22") (pin "2") (pintype "passive"))
      (node (ref "C23") (pin "2") (pintype "passive"))
      (node (ref "C24") (pin "2") (pintype "passive"))
      (node (ref "C25") (pin "2") (pintype "passive"))
      (node (ref "C26") (pin "2") (pintype "passive"))
      (node (ref "CN7") (pin "1") (pinfunction "VCC_1") (pintype "power_in"))
      (node (ref "FB1") (pin "2") (pintype "passive"))
      (node (ref "Q9") (pin "2") (pinfunction "S_2") (pintype "passive"))
      (node (ref "R18") (pin "2") (pinfunction "2_2") (pintype "passive"))
      (node (ref "R22") (pin "1") (pinfunction "1_1") (pintype "passive"))
      (node (ref "R23") (pin "1") (pinfunction "1_1") (pintype "passive"))
      (node (ref "R24") (pin "2") (pinfunction "2_2") (pintype "passive"))
      (node (ref "R26") (pin "2") (pinfunction "2_2") (pintype "passive"))
      (node (ref "U3") (pin "100") (pinfunction "VDD_100") (pintype "power_in"))
      (node (ref "U3") (pin "11") (pinfunction "VDD_11") (pintype "power_in"))
      (node (ref "U3") (pin "28") (pinfunction "VDD_28") (pintype "power_in"))
      (node (ref "U3") (pin "50") (pinfunction "VDD_50") (pintype "power_in"))
      (node (ref "U3") (pin "75") (pinfunction "VDD_75") (pintype "power_in"))
      (node (ref "U4") (pin "1") (pinfunction "VIN_1") (pintype "power_in"))
      (node (ref "Z1") (pin "1") (pinfunction "1_1") (pintype "passive"))
      (node (ref "Z1") (pin "2") (pinfunction "2_2") (pintype "passive"))
    )
    (net (code "95") (name "VDD_M1") (class "Default")
      (node (ref "M1") (pin "15") (pinfunction "3.3V_15") (pintype "passive"))
      (node (ref "Q9") (pin "3") (pinfunction "D_3") (pintype "passive"))
    )
    (net (code "96") (name "unconnected-(U3-PB12-Pad51)") (class "Default")
      (node (ref "U3") (pin "51") (pinfunction "PB12_51") (pintype "passive+no_connect"))
    )
    (net (code "97") (name "unconnected-(U3-PC2-Pad17)") (class "Default")
      (node (ref "U3") (pin "17") (pinfunction "PC2_17") (pintype "passive+no_connect"))
    )
    (net (code "98") (name "unconnected-(U3-PC3-Pad18)") (class "Default")
      (node (ref "U3") (pin "18") (pinfunction "PC3_18") (pintype "passive+no_connect"))
    )
    (net (code "99") (name "unconnected-(U3-PC13-Pad7)") (class "Default")
      (node (ref "U3") (pin "7") (pinfunction "PC13_7") (pintype "passive+no_connect"))
    )
    (net (code "100") (name "unconnected-(U3-PD3-Pad84)") (class "Default")
      (node (ref "U3") (pin "84") (pinfunction "PD3_84") (pintype "passive+no_connect"))
    )
    (net (code "101") (name "unconnected-(U3-PD7-Pad88)") (class "Default")
      (node (ref "U3") (pin "88") (pinfunction "PD7_88") (pintype "passive+no_connect"))
    )
    (net (code "102") (name "unconnected-(U3-PD10-Pad57)") (class "Default")
      (node (ref "U3") (pin "57") (pinfunction "PD10_57") (pintype "passive+no_connect"))
    )
    (net (code "103") (name "unconnected-(U3-PE4-Pad3)") (class "Default")
      (node (ref "U3") (pin "3") (pinfunction "PE4_3") (pintype "passive+no_connect"))
    )
    (net (code "104") (name "unconnected-(U3-PE11-Pad42)") (class "Default")
      (node (ref "U3") (pin "42") (pinfunction "PE11_42") (pintype "passive+no_connect"))
    )
  )
)
